# remote.net
KiCad netlist of a schematic drawn in EAGLE
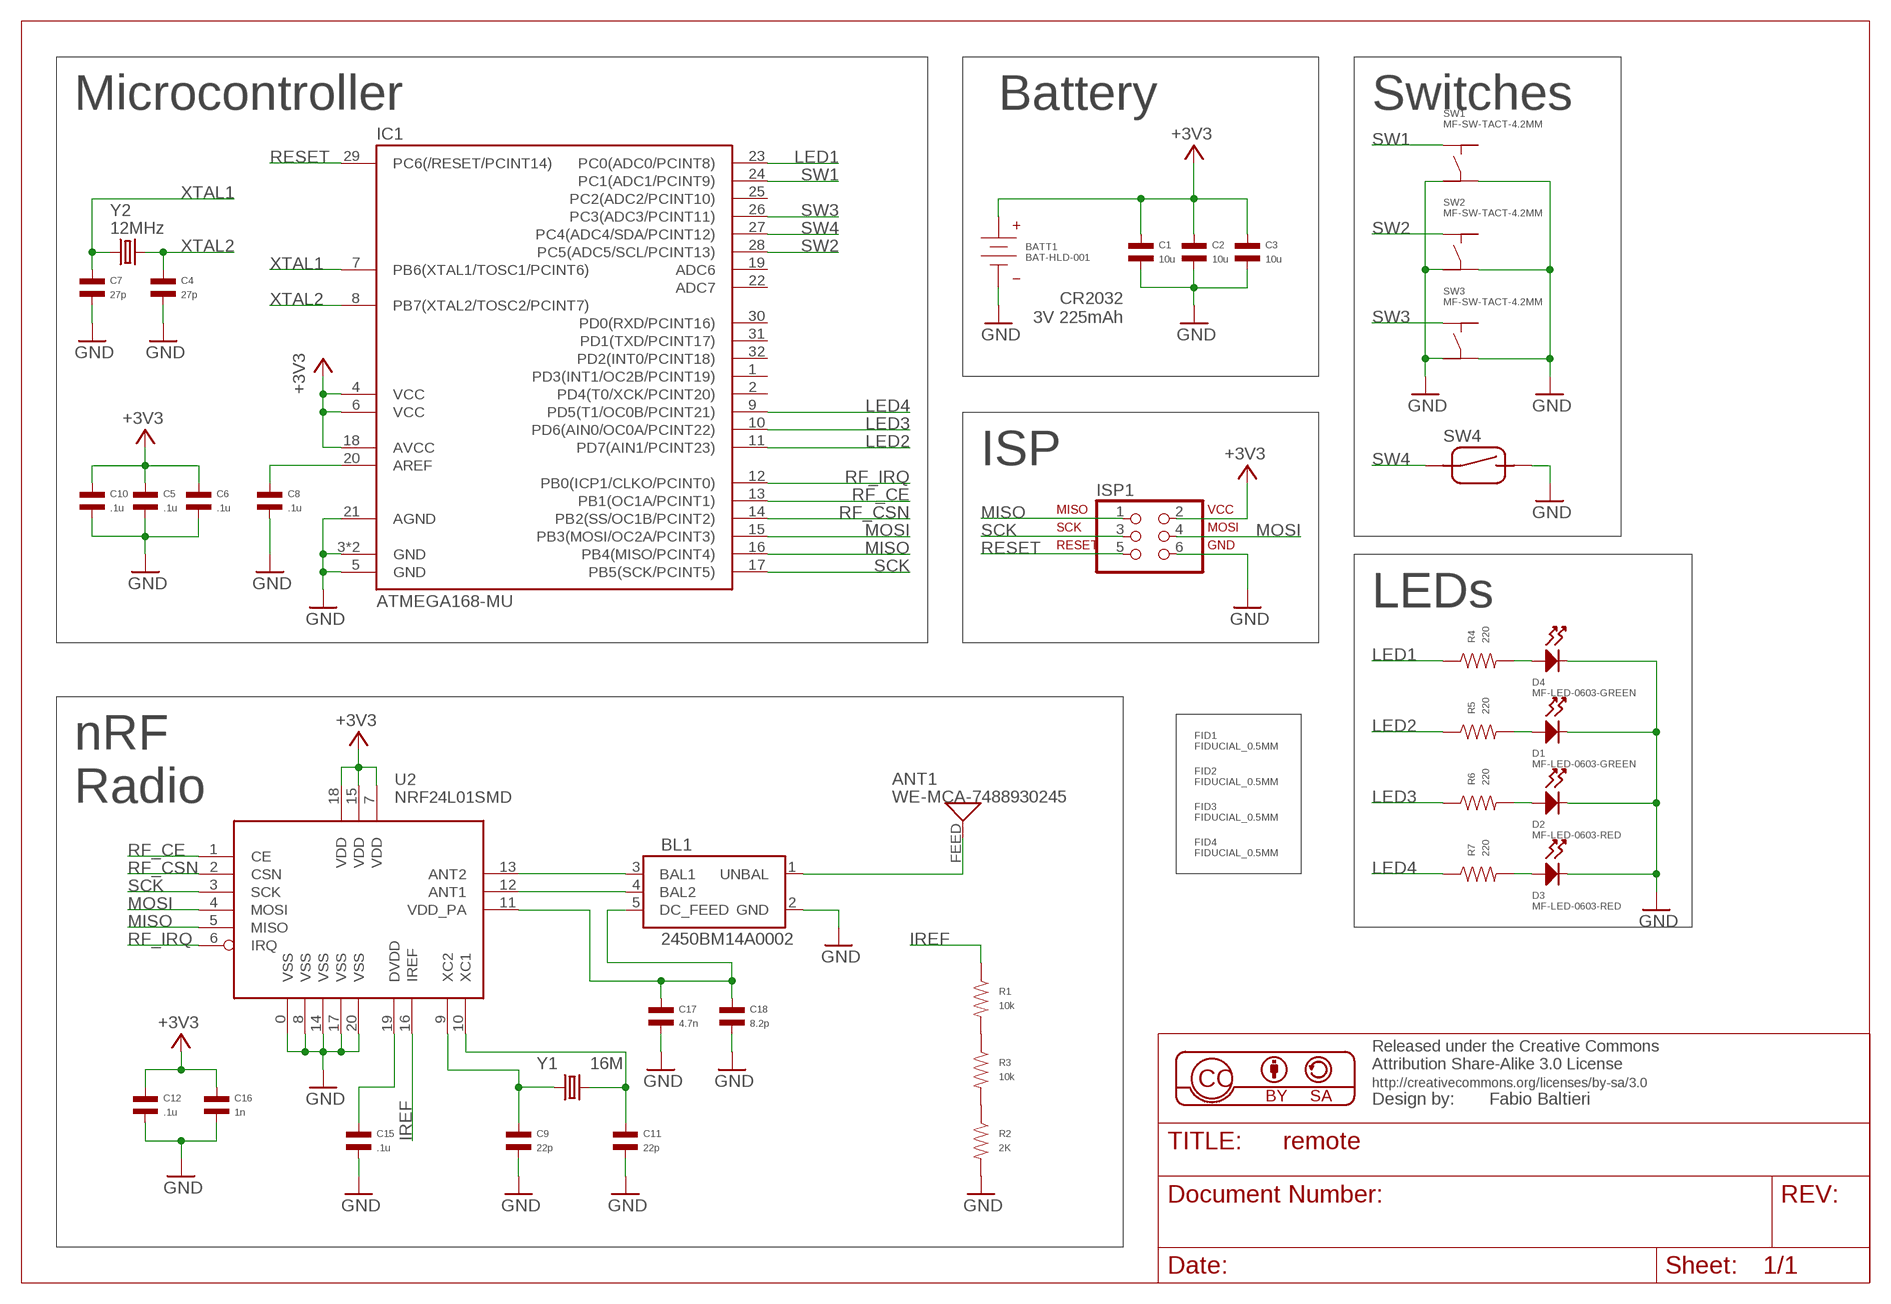
[diagram p0: schematic, sheet 1]

(export (version "E")
  (design (tool "Eeschema 10.0.6"))
  (components
    (comp (ref "ANT1")
      (value "WE-MCA-7488930245")
      (footprint "eagle-import:WE-MCA")
      (libsource (lib "eagle-import") (part "WE-MCA-7488930245"))
    )
    (comp (ref "BATT1")
      (value "BAT-HLD-001")
      (footprint "eagle-import:BAT-HLD-001")
      (fields (field (name "HOUSEPART") "NO"))
      (libsource (lib "eagle-import") (part "BATTERY_BAT-HLD-001"))
    )
    (comp (ref "BL1")
      (value "2450BM14A0002")
      (footprint "eagle-import:0603_BALUN")
      (libsource (lib "eagle-import") (part "2450BM14A0002"))
    )
    (comp (ref "C1")
      (value "10u")
      (footprint "eagle-import:C1206")
      (fields (field (name "MPN") "MF-CAP-1206-10uF"))
      (libsource (lib "eagle-import") (part "CAPACITOR_NP_1206"))
    )
    (comp (ref "C2")
      (value "10u")
      (footprint "eagle-import:C1206")
      (fields (field (name "MPN") "MF-CAP-1206-10uF"))
      (libsource (lib "eagle-import") (part "CAPACITOR_NP_1206"))
    )
    (comp (ref "C3")
      (value "10u")
      (footprint "eagle-import:C1206")
      (fields (field (name "MPN") "MF-CAP-1206-10uF"))
      (libsource (lib "eagle-import") (part "CAPACITOR_NP_1206"))
    )
    (comp (ref "C4")
      (value "27p")
      (footprint "eagle-import:C0402")
      (fields (field (name "MPN") "MF-CAP-0402-27p"))
      (libsource (lib "eagle-import") (part "CAPACITOR_NP_0402"))
    )
    (comp (ref "C5")
      (value ".1u")
      (footprint "eagle-import:C0402")
      (fields (field (name "MPN") "MF-CAP-0402-0.1uF"))
      (libsource (lib "eagle-import") (part "CAPACITOR_NP_0402"))
    )
    (comp (ref "C6")
      (value ".1u")
      (footprint "eagle-import:C0402")
      (fields (field (name "MPN") "MF-CAP-0402-0.1uF"))
      (libsource (lib "eagle-import") (part "CAPACITOR_NP_0402"))
    )
    (comp (ref "C7")
      (value "27p")
      (footprint "eagle-import:C0402")
      (fields (field (name "MPN") "MF-CAP-0402-27p"))
      (libsource (lib "eagle-import") (part "CAPACITOR_NP_0402"))
    )
    (comp (ref "C8")
      (value ".1u")
      (footprint "eagle-import:C0402")
      (fields (field (name "MPN") "MF-CAP-0402-0.1uF"))
      (libsource (lib "eagle-import") (part "CAPACITOR_NP_0402"))
    )
    (comp (ref "C9")
      (value "22p")
      (footprint "eagle-import:C0402")
      (fields (field (name "MPN") "MF-CAP-0402-22p"))
      (libsource (lib "eagle-import") (part "CAPACITOR_NP_0402"))
    )
    (comp (ref "C10")
      (value ".1u")
      (footprint "eagle-import:C0402")
      (fields (field (name "MPN") "MF-CAP-0402-0.1uF"))
      (libsource (lib "eagle-import") (part "CAPACITOR_NP_0402"))
    )
    (comp (ref "C11")
      (value "22p")
      (footprint "eagle-import:C0402")
      (fields (field (name "MPN") "MF-CAP-0402-22p"))
      (libsource (lib "eagle-import") (part "CAPACITOR_NP_0402"))
    )
    (comp (ref "C12")
      (value ".1u")
      (footprint "eagle-import:C0402")
      (fields (field (name "MPN") "MF-CAP-0402-0.1uF"))
      (libsource (lib "eagle-import") (part "CAPACITOR_NP_0402"))
    )
    (comp (ref "C15")
      (value ".1u")
      (footprint "eagle-import:C0402")
      (fields (field (name "MPN") "MF-CAP-0402-0.1uF"))
      (libsource (lib "eagle-import") (part "CAPACITOR_NP_0402"))
    )
    (comp (ref "C16")
      (value "1n")
      (footprint "eagle-import:C0402")
      (fields (field (name "MPN") "MF-CAP-0402-1nF"))
      (libsource (lib "eagle-import") (part "CAPACITOR_NP_0402"))
    )
    (comp (ref "C17")
      (value "4.7n")
      (footprint "eagle-import:C0402")
      (fields (field (name "MPN") "MF-CAP-0402-4.7nF"))
      (libsource (lib "eagle-import") (part "CAPACITOR_NP_0402"))
    )
    (comp (ref "C18")
      (value "8.2p")
      (footprint "eagle-import:C0402")
      (fields (field (name "MPN") "MF-CAP-0402-8.2pF"))
      (libsource (lib "eagle-import") (part "CAPACITOR_NP_0402"))
    )
    (comp (ref "D1")
      (value "MF-LED-0603-GREEN")
      (footprint "eagle-import:LED0603")
      (fields (field (name "HOUSEPART") "YES"))
      (libsource (lib "eagle-import") (part "LED_SINGLE-0603-GREEN"))
    )
    (comp (ref "D2")
      (value "MF-LED-0603-RED")
      (footprint "eagle-import:LED0603")
      (fields (field (name "HOUSEPART") "YES"))
      (libsource (lib "eagle-import") (part "LED_SINGLE-0603-RED"))
    )
    (comp (ref "D3")
      (value "MF-LED-0603-RED")
      (footprint "eagle-import:LED0603")
      (fields (field (name "HOUSEPART") "YES"))
      (libsource (lib "eagle-import") (part "LED_SINGLE-0603-RED"))
    )
    (comp (ref "D4")
      (value "MF-LED-0603-GREEN")
      (footprint "eagle-import:LED0603")
      (fields (field (name "HOUSEPART") "YES"))
      (libsource (lib "eagle-import") (part "LED_SINGLE-0603-GREEN"))
    )
    (comp (ref "FID1")
      (value "FIDUCIAL_0.5MM")
      (footprint "eagle-import:FIDUCIAL_0.5MM")
      (fields (field (name "HOUSEPART") "NO"))
      (libsource (lib "eagle-import") (part "FIDUCIAL_0.5MM"))
    )
    (comp (ref "FID2")
      (value "FIDUCIAL_0.5MM")
      (footprint "eagle-import:FIDUCIAL_0.5MM")
      (fields (field (name "HOUSEPART") "NO"))
      (libsource (lib "eagle-import") (part "FIDUCIAL_0.5MM"))
    )
    (comp (ref "FID3")
      (value "FIDUCIAL_0.5MM")
      (footprint "eagle-import:FIDUCIAL_0.5MM")
      (fields (field (name "HOUSEPART") "NO"))
      (libsource (lib "eagle-import") (part "FIDUCIAL_0.5MM"))
    )
    (comp (ref "FID4")
      (value "FIDUCIAL_0.5MM")
      (footprint "eagle-import:FIDUCIAL_0.5MM")
      (fields (field (name "HOUSEPART") "NO"))
      (libsource (lib "eagle-import") (part "FIDUCIAL_0.5MM"))
    )
    (comp (ref "IC1")
      (value "ATMEGA168-MU")
      (footprint "eagle-import:MLF32-TH")
      (libsource (lib "eagle-import") (part "ATMEGA168-MU"))
    )
    (comp (ref "ISP1")
      (value "ISP-AVR910PTH")
      (footprint "eagle-import:2X03")
      (libsource (lib "eagle-import") (part "ISP-AVR910PTH"))
    )
    (comp (ref "R1")
      (value "10k")
      (footprint "eagle-import:R0402")
      (fields (field (name "MPN") "MF-RES-0402-10K"))
      (libsource (lib "eagle-import") (part "RESISTOR_0402"))
    )
    (comp (ref "R2")
      (value "2K")
      (footprint "eagle-import:R0402")
      (fields (field (name "MPN") "MF-RES-0402-2K"))
      (libsource (lib "eagle-import") (part "RESISTOR_0402"))
    )
    (comp (ref "R3")
      (value "10k")
      (footprint "eagle-import:R0402")
      (fields (field (name "MPN") "MF-RES-0402-10K"))
      (libsource (lib "eagle-import") (part "RESISTOR_0402"))
    )
    (comp (ref "R4")
      (value "220")
      (footprint "eagle-import:R0402")
      (fields (field (name "MPN") "MF-RES-0402-220"))
      (libsource (lib "eagle-import") (part "RESISTOR_0402"))
    )
    (comp (ref "R5")
      (value "220")
      (footprint "eagle-import:R0402")
      (fields (field (name "MPN") "MF-RES-0402-220"))
      (libsource (lib "eagle-import") (part "RESISTOR_0402"))
    )
    (comp (ref "R6")
      (value "220")
      (footprint "eagle-import:R0402")
      (fields (field (name "MPN") "MF-RES-0402-220"))
      (libsource (lib "eagle-import") (part "RESISTOR_0402"))
    )
    (comp (ref "R7")
      (value "220")
      (footprint "eagle-import:R0402")
      (fields (field (name "MPN") "MF-RES-0402-220"))
      (libsource (lib "eagle-import") (part "RESISTOR_0402"))
    )
    (comp (ref "SW1")
      (value "MF-SW-TACT-4.2MM")
      (footprint "eagle-import:TACT4.2MM")
      (fields (field (name "HOUSEPART") "YES"))
      (libsource (lib "eagle-import") (part "TACT_4.2MM"))
    )
    (comp (ref "SW2")
      (value "MF-SW-TACT-4.2MM")
      (footprint "eagle-import:TACT4.2MM")
      (fields (field (name "HOUSEPART") "YES"))
      (libsource (lib "eagle-import") (part "TACT_4.2MM"))
    )
    (comp (ref "SW3")
      (value "MF-SW-TACT-4.2MM")
      (footprint "eagle-import:TACT4.2MM")
      (fields (field (name "HOUSEPART") "YES"))
      (libsource (lib "eagle-import") (part "TACT_4.2MM"))
    )
    (comp (ref "SW4")
      (value "CT05-XXXX-J1")
      (footprint "eagle-import:CT05-XXXX-J1")
      (libsource (lib "eagle-import") (part "CT05-XXXX-J1"))
    )
    (comp (ref "U2")
      (value "NRF24L01SMD")
      (footprint "eagle-import:QFN20")
      (libsource (lib "eagle-import") (part "NRF24L01SMD"))
    )
    (comp (ref "Y1")
      (value "16M")
      (footprint "eagle-import:CRYSTAL-SMD-5X3")
      (libsource (lib "eagle-import") (part "CRYSTAL5X3"))
    )
    (comp (ref "Y2")
      (value "12MHz")
      (footprint "eagle-import:CRYSTAL-SMD-5X3")
      (libsource (lib "eagle-import") (part "SparkFun-FreqCtrl_CRYSTAL5X3"))
    )
  )
  (nets
    (net (code "1") (name "+3V3") (class "Default")
      (node (ref "BATT1") (pin "POS_0") (pinfunction "POS_POS_0") (pintype "bidirectional"))
      (node (ref "BATT1") (pin "POS_1") (pinfunction "POS_POS_1") (pintype "bidirectional"))
      (node (ref "C1") (pin "P$1") (pinfunction "P$1_P$1") (pintype "passive"))
      (node (ref "C10") (pin "P$1") (pinfunction "P$1_P$1") (pintype "passive"))
      (node (ref "C12") (pin "P$1") (pinfunction "P$1_P$1") (pintype "passive"))
      (node (ref "C16") (pin "P$1") (pinfunction "P$1_P$1") (pintype "passive"))
      (node (ref "C2") (pin "P$1") (pinfunction "P$1_P$1") (pintype "passive"))
      (node (ref "C3") (pin "P$1") (pinfunction "P$1_P$1") (pintype "passive"))
      (node (ref "C5") (pin "P$1") (pinfunction "P$1_P$1") (pintype "passive"))
      (node (ref "C6") (pin "P$1") (pinfunction "P$1_P$1") (pintype "passive"))
      (node (ref "IC1") (pin "18") (pinfunction "AVCC_18") (pintype "passive"))
      (node (ref "IC1") (pin "4") (pinfunction "VCC_4") (pintype "power_in"))
      (node (ref "IC1") (pin "6") (pinfunction "VCC_6") (pintype "power_in"))
      (node (ref "ISP1") (pin "2") (pinfunction "2_2") (pintype "passive"))
      (node (ref "U2") (pin "15") (pinfunction "VDD_15") (pintype "power_in"))
      (node (ref "U2") (pin "18") (pinfunction "VDD_18") (pintype "power_in"))
      (node (ref "U2") (pin "7") (pinfunction "VDD_7") (pintype "power_in"))
    )
    (net (code "2") (name "/IREF") (class "Default")
      (node (ref "R1") (pin "P$1") (pinfunction "P$1_P$1") (pintype "passive"))
      (node (ref "U2") (pin "16") (pinfunction "IREF_16") (pintype "input"))
    )
    (net (code "3") (name "/LED1") (class "Default")
      (node (ref "IC1") (pin "23") (pinfunction "PC0(ADC0/PCINT8)_23") (pintype "bidirectional"))
      (node (ref "R4") (pin "P$1") (pinfunction "P$1_P$1") (pintype "passive"))
    )
    (net (code "4") (name "/LED2") (class "Default")
      (node (ref "IC1") (pin "11") (pinfunction "PD7(AIN1/PCINT23)_11") (pintype "bidirectional"))
      (node (ref "R5") (pin "P$1") (pinfunction "P$1_P$1") (pintype "passive"))
    )
    (net (code "5") (name "/LED3") (class "Default")
      (node (ref "IC1") (pin "10") (pinfunction "PD6(AIN0/OC0A/PCINT22)_10") (pintype "bidirectional"))
      (node (ref "R6") (pin "P$1") (pinfunction "P$1_P$1") (pintype "passive"))
    )
    (net (code "6") (name "/LED4") (class "Default")
      (node (ref "IC1") (pin "9") (pinfunction "PD5(T1/OC0B/PCINT21)_9") (pintype "bidirectional"))
      (node (ref "R7") (pin "P$1") (pinfunction "P$1_P$1") (pintype "passive"))
    )
    (net (code "7") (name "/MISO") (class "Default")
      (node (ref "IC1") (pin "16") (pinfunction "PB4(MISO/PCINT4)_16") (pintype "bidirectional"))
      (node (ref "ISP1") (pin "1") (pinfunction "1_1") (pintype "passive"))
      (node (ref "U2") (pin "5") (pinfunction "MISO_5") (pintype "output"))
    )
    (net (code "8") (name "/MOSI") (class "Default")
      (node (ref "IC1") (pin "15") (pinfunction "PB3(MOSI/OC2A/PCINT3)_15") (pintype "bidirectional"))
      (node (ref "ISP1") (pin "4") (pinfunction "4_4") (pintype "passive"))
      (node (ref "U2") (pin "4") (pinfunction "MOSI_4") (pintype "input"))
    )
    (net (code "9") (name "/RESET") (class "Default")
      (node (ref "IC1") (pin "29") (pinfunction "PC6(/RESET/PCINT14)_29") (pintype "bidirectional"))
      (node (ref "ISP1") (pin "5") (pinfunction "5_5") (pintype "passive"))
    )
    (net (code "10") (name "/RF_CE") (class "Default")
      (node (ref "IC1") (pin "13") (pinfunction "PB1(OC1A/PCINT1)_13") (pintype "bidirectional"))
      (node (ref "U2") (pin "1") (pinfunction "CE_1") (pintype "input"))
    )
    (net (code "11") (name "/RF_CSN") (class "Default")
      (node (ref "IC1") (pin "14") (pinfunction "PB2(SS/OC1B/PCINT2)_14") (pintype "bidirectional"))
      (node (ref "U2") (pin "2") (pinfunction "CSN_2") (pintype "input"))
    )
    (net (code "12") (name "/RF_IRQ") (class "Default")
      (node (ref "IC1") (pin "12") (pinfunction "PB0(ICP1/CLKO/PCINT0)_12") (pintype "bidirectional"))
      (node (ref "U2") (pin "6") (pinfunction "IRQ_6") (pintype "output"))
    )
    (net (code "13") (name "/SCK") (class "Default")
      (node (ref "IC1") (pin "17") (pinfunction "PB5(SCK/PCINT5)_17") (pintype "bidirectional"))
      (node (ref "ISP1") (pin "3") (pinfunction "3_3") (pintype "passive"))
      (node (ref "U2") (pin "3") (pinfunction "SCK_3") (pintype "input"))
    )
    (net (code "14") (name "/SW1") (class "Default")
      (node (ref "IC1") (pin "24") (pinfunction "PC1(ADC1/PCINT9)_24") (pintype "bidirectional"))
      (node (ref "SW1") (pin "P$1") (pinfunction "P$1_P$1") (pintype "bidirectional"))
    )
    (net (code "15") (name "/SW2") (class "Default")
      (node (ref "IC1") (pin "28") (pinfunction "PC5(ADC5/SCL/PCINT13)_28") (pintype "bidirectional"))
      (node (ref "SW2") (pin "P$1") (pinfunction "P$1_P$1") (pintype "bidirectional"))
    )
    (net (code "16") (name "/SW3") (class "Default")
      (node (ref "IC1") (pin "26") (pinfunction "PC3(ADC3/PCINT11)_26") (pintype "bidirectional"))
      (node (ref "SW3") (pin "P$1") (pinfunction "P$1_P$1") (pintype "bidirectional"))
    )
    (net (code "17") (name "/SW4") (class "Default")
      (node (ref "IC1") (pin "27") (pinfunction "PC4(ADC4/SDA/PCINT12)_27") (pintype "bidirectional"))
      (node (ref "SW4") (pin "P$1") (pinfunction "A_P$1") (pintype "bidirectional"))
    )
    (net (code "18") (name "/XTAL1") (class "Default")
      (node (ref "C7") (pin "P$1") (pinfunction "P$1_P$1") (pintype "passive"))
      (node (ref "IC1") (pin "7") (pinfunction "PB6(XTAL1/TOSC1/PCINT6)_7") (pintype "bidirectional"))
      (node (ref "Y2") (pin "1") (pinfunction "1_1") (pintype "passive"))
    )
    (net (code "19") (name "/XTAL2") (class "Default")
      (node (ref "C4") (pin "P$1") (pinfunction "P$1_P$1") (pintype "passive"))
      (node (ref "IC1") (pin "8") (pinfunction "PB7(XTAL2/TOSC2/PCINT7)_8") (pintype "bidirectional"))
      (node (ref "Y2") (pin "3") (pinfunction "2_3") (pintype "passive"))
    )
    (net (code "20") (name "GND") (class "Default")
      (node (ref "BATT1") (pin "NEG_0") (pinfunction "NEG_NEG_0") (pintype "bidirectional"))
      (node (ref "BL1") (pin "2") (pinfunction "GND_2") (pintype "bidirectional"))
      (node (ref "C1") (pin "P$2") (pinfunction "P$2_P$2") (pintype "passive"))
      (node (ref "C10") (pin "P$2") (pinfunction "P$2_P$2") (pintype "passive"))
      (node (ref "C11") (pin "P$2") (pinfunction "P$2_P$2") (pintype "passive"))
      (node (ref "C12") (pin "P$2") (pinfunction "P$2_P$2") (pintype "passive"))
      (node (ref "C15") (pin "P$2") (pinfunction "P$2_P$2") (pintype "passive"))
      (node (ref "C16") (pin "P$2") (pinfunction "P$2_P$2") (pintype "passive"))
      (node (ref "C17") (pin "P$2") (pinfunction "P$2_P$2") (pintype "passive"))
      (node (ref "C18") (pin "P$2") (pinfunction "P$2_P$2") (pintype "passive"))
      (node (ref "C2") (pin "P$2") (pinfunction "P$2_P$2") (pintype "passive"))
      (node (ref "C3") (pin "P$2") (pinfunction "P$2_P$2") (pintype "passive"))
      (node (ref "C4") (pin "P$2") (pinfunction "P$2_P$2") (pintype "passive"))
      (node (ref "C5") (pin "P$2") (pinfunction "P$2_P$2") (pintype "passive"))
      (node (ref "C6") (pin "P$2") (pinfunction "P$2_P$2") (pintype "passive"))
      (node (ref "C7") (pin "P$2") (pinfunction "P$2_P$2") (pintype "passive"))
      (node (ref "C8") (pin "P$2") (pinfunction "P$2_P$2") (pintype "passive"))
      (node (ref "C9") (pin "P$2") (pinfunction "P$2_P$2") (pintype "passive"))
      (node (ref "D1") (pin "CATHODE") (pinfunction "CATHODE_CATHODE") (pintype "power_in"))
      (node (ref "D2") (pin "CATHODE") (pinfunction "CATHODE_CATHODE") (pintype "power_in"))
      (node (ref "D3") (pin "CATHODE") (pinfunction "CATHODE_CATHODE") (pintype "power_in"))
      (node (ref "D4") (pin "CATHODE") (pinfunction "CATHODE_CATHODE") (pintype "power_in"))
      (node (ref "IC1") (pin "21") (pinfunction "AGND_21") (pintype "power_in"))
      (node (ref "IC1") (pin "3") (pinfunction "GND_3") (pintype "power_in"))
      (node (ref "IC1") (pin "5") (pinfunction "GND_5") (pintype "power_in"))
      (node (ref "IC1") (pin "TH") (pinfunction "GND_TH") (pintype "power_in"))
      (node (ref "ISP1") (pin "6") (pinfunction "6_6") (pintype "passive"))
      (node (ref "R2") (pin "P$2") (pinfunction "P$2_P$2") (pintype "passive"))
      (node (ref "SW1") (pin "P$3") (pinfunction "P$3_P$3") (pintype "bidirectional"))
      (node (ref "SW1") (pin "P$4") (pinfunction "P$4_P$4") (pintype "bidirectional"))
      (node (ref "SW2") (pin "P$3") (pinfunction "P$3_P$3") (pintype "bidirectional"))
      (node (ref "SW2") (pin "P$4") (pinfunction "P$4_P$4") (pintype "bidirectional"))
      (node (ref "SW3") (pin "P$3") (pinfunction "P$3_P$3") (pintype "bidirectional"))
      (node (ref "SW3") (pin "P$4") (pinfunction "P$4_P$4") (pintype "bidirectional"))
      (node (ref "SW4") (pin "P$2") (pinfunction "B_P$2") (pintype "bidirectional"))
      (node (ref "U2") (pin "0") (pinfunction "VSS_0") (pintype "power_in"))
      (node (ref "U2") (pin "14") (pinfunction "VSS_14") (pintype "power_in"))
      (node (ref "U2") (pin "17") (pinfunction "VSS_17") (pintype "power_in"))
      (node (ref "U2") (pin "20") (pinfunction "VSS_20") (pintype "power_in"))
      (node (ref "U2") (pin "8") (pinfunction "VSS_8") (pintype "power_in"))
    )
    (net (code "21") (name "Net-(ANT1-P$1)") (class "Default")
      (node (ref "ANT1") (pin "FEED") (pinfunction "P$1_FEED") (pintype "bidirectional"))
      (node (ref "BL1") (pin "1") (pinfunction "UNBAL_1") (pintype "bidirectional"))
    )
    (net (code "22") (name "Net-(BL1-BAL1)") (class "Default")
      (node (ref "BL1") (pin "3") (pinfunction "BAL1_3") (pintype "bidirectional"))
      (node (ref "U2") (pin "13") (pinfunction "ANT2_13") (pintype "output"))
    )
    (net (code "23") (name "Net-(BL1-BAL2)") (class "Default")
      (node (ref "BL1") (pin "4") (pinfunction "BAL2_4") (pintype "bidirectional"))
      (node (ref "U2") (pin "12") (pinfunction "ANT1_12") (pintype "output"))
    )
    (net (code "24") (name "Net-(BL1-DC_FEED)") (class "Default")
      (node (ref "BL1") (pin "5") (pinfunction "DC_FEED_5") (pintype "bidirectional"))
      (node (ref "C17") (pin "P$1") (pinfunction "P$1_P$1") (pintype "passive"))
      (node (ref "C18") (pin "P$1") (pinfunction "P$1_P$1") (pintype "passive"))
      (node (ref "U2") (pin "11") (pinfunction "VDD_PA_11") (pintype "power_in"))
    )
    (net (code "25") (name "Net-(D1-PadANODE)") (class "Default")
      (node (ref "D1") (pin "ANODE") (pinfunction "ANODE_ANODE") (pintype "power_in"))
      (node (ref "R5") (pin "P$2") (pinfunction "P$2_P$2") (pintype "passive"))
    )
    (net (code "26") (name "Net-(D2-PadANODE)") (class "Default")
      (node (ref "D2") (pin "ANODE") (pinfunction "ANODE_ANODE") (pintype "power_in"))
      (node (ref "R6") (pin "P$2") (pinfunction "P$2_P$2") (pintype "passive"))
    )
    (net (code "27") (name "Net-(D3-PadANODE)") (class "Default")
      (node (ref "D3") (pin "ANODE") (pinfunction "ANODE_ANODE") (pintype "power_in"))
      (node (ref "R7") (pin "P$2") (pinfunction "P$2_P$2") (pintype "passive"))
    )
    (net (code "28") (name "Net-(D4-PadANODE)") (class "Default")
      (node (ref "D4") (pin "ANODE") (pinfunction "ANODE_ANODE") (pintype "power_in"))
      (node (ref "R4") (pin "P$2") (pinfunction "P$2_P$2") (pintype "passive"))
    )
    (net (code "29") (name "Net-(IC1-AREF)") (class "Default")
      (node (ref "C8") (pin "P$1") (pinfunction "P$1_P$1") (pintype "passive"))
      (node (ref "IC1") (pin "20") (pinfunction "AREF_20") (pintype "passive"))
    )
    (net (code "30") (name "Net-(R1-PadP$2)") (class "Default")
      (node (ref "R1") (pin "P$2") (pinfunction "P$2_P$2") (pintype "passive"))
      (node (ref "R3") (pin "P$1") (pinfunction "P$1_P$1") (pintype "passive"))
    )
    (net (code "31") (name "Net-(R2-PadP$1)") (class "Default")
      (node (ref "R2") (pin "P$1") (pinfunction "P$1_P$1") (pintype "passive"))
      (node (ref "R3") (pin "P$2") (pinfunction "P$2_P$2") (pintype "passive"))
    )
    (net (code "32") (name "Net-(U2-DVDD)") (class "Default")
      (node (ref "C15") (pin "P$1") (pinfunction "P$1_P$1") (pintype "passive"))
      (node (ref "U2") (pin "19") (pinfunction "DVDD_19") (pintype "power_in"))
    )
    (net (code "33") (name "Net-(U2-XC1)") (class "Default")
      (node (ref "C11") (pin "P$1") (pinfunction "P$1_P$1") (pintype "passive"))
      (node (ref "U2") (pin "10") (pinfunction "XC1_10") (pintype "input"))
      (node (ref "Y1") (pin "3") (pinfunction "2_3") (pintype "passive"))
    )
    (net (code "34") (name "Net-(U2-XC2)") (class "Default")
      (node (ref "C9") (pin "P$1") (pinfunction "P$1_P$1") (pintype "passive"))
      (node (ref "U2") (pin "9") (pinfunction "XC2_9") (pintype "input"))
      (node (ref "Y1") (pin "1") (pinfunction "1_1") (pintype "passive"))
    )
    (net (code "35") (name "unconnected-(IC1-ADC6-Pad19)") (class "Default")
      (node (ref "IC1") (pin "19") (pinfunction "ADC6_19") (pintype "passive"))
    )
    (net (code "36") (name "unconnected-(IC1-ADC7-Pad22)") (class "Default")
      (node (ref "IC1") (pin "22") (pinfunction "ADC7_22") (pintype "passive"))
    )
    (net (code "37") (name "unconnected-(IC1-PC2(ADC2{slash}PCINT10)-Pad25)") (class "Default")
      (node (ref "IC1") (pin "25") (pinfunction "PC2(ADC2/PCINT10)_25") (pintype "bidirectional"))
    )
    (net (code "38") (name "unconnected-(IC1-PD0(RXD{slash}PCINT16)-Pad30)") (class "Default")
      (node (ref "IC1") (pin "30") (pinfunction "PD0(RXD/PCINT16)_30") (pintype "bidirectional"))
    )
    (net (code "39") (name "unconnected-(IC1-PD1(TXD{slash}PCINT17)-Pad31)") (class "Default")
      (node (ref "IC1") (pin "31") (pinfunction "PD1(TXD/PCINT17)_31") (pintype "bidirectional"))
    )
    (net (code "40") (name "unconnected-(IC1-PD2(INT0{slash}PCINT18)-Pad32)") (class "Default")
      (node (ref "IC1") (pin "32") (pinfunction "PD2(INT0/PCINT18)_32") (pintype "bidirectional"))
    )
    (net (code "41") (name "unconnected-(IC1-PD3(INT1{slash}OC2B{slash}PCINT19)-Pad1)") (class "Default")
      (node (ref "IC1") (pin "1") (pinfunction "PD3(INT1/OC2B/PCINT19)_1") (pintype "bidirectional"))
    )
    (net (code "42") (name "unconnected-(IC1-PD4(T0{slash}XCK{slash}PCINT20)-Pad2)") (class "Default")
      (node (ref "IC1") (pin "2") (pinfunction "PD4(T0/XCK/PCINT20)_2") (pintype "bidirectional"))
    )
    (net (code "43") (name "unconnected-(SW1-PadP$2)") (class "Default")
      (node (ref "SW1") (pin "P$2") (pinfunction "P$2_P$2") (pintype "bidirectional"))
    )
    (net (code "44") (name "unconnected-(SW2-PadP$2)") (class "Default")
      (node (ref "SW2") (pin "P$2") (pinfunction "P$2_P$2") (pintype "bidirectional"))
    )
    (net (code "45") (name "unconnected-(SW3-PadP$2)") (class "Default")
      (node (ref "SW3") (pin "P$2") (pinfunction "P$2_P$2") (pintype "bidirectional"))
    )
  )
)
